# CON_PCI_Express_X1_36PIN.net
KiCad netlist of a schematic drawn in Altium Designer
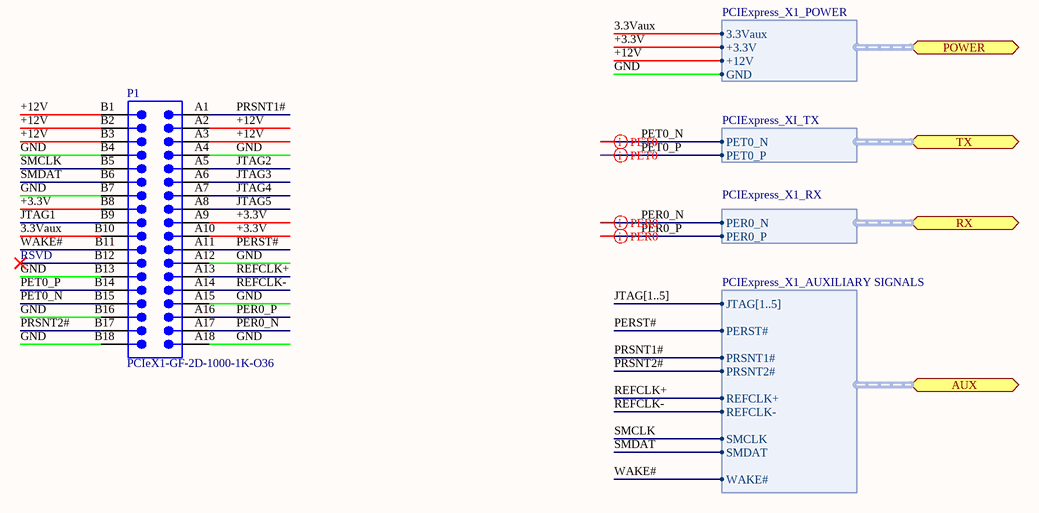
[diagram p0: CON_PCI_Express_X1_36PIN.SchDoc]

(export (version "E")
  (design (tool "Eeschema 10.0.6"))
  (components
    (comp (ref "P1")
      (value "PCIeX1-GF-2D-1000-1K-O36")
      (footprint "PCIeX1-GF-2D-1000-1K-O36")
      (description "Golden finger, PCIeX1, Dual, Opposite, Pitch 1mm, 36-Position")
      (fields (field (name "PUBLISHER") "Altium"))
      (libsource (lib "Altium Shanghai") (part "CMP-0001-00030-2"))
    )
  )
  (nets
    (net (code "6") (name "/+3.3V") (class "Default")
      (node (ref "P1") (pin "A10") (pinfunction "A10_A10") (pintype "passive"))
      (node (ref "P1") (pin "A9") (pinfunction "A9_A9") (pintype "passive"))
      (node (ref "P1") (pin "B8") (pinfunction "B8_B8") (pintype "passive"))
    )
    (net (code "7") (name "/+12V") (class "Default")
      (node (ref "P1") (pin "A2") (pinfunction "A2_A2") (pintype "passive"))
      (node (ref "P1") (pin "A3") (pinfunction "A3_A3") (pintype "passive"))
      (node (ref "P1") (pin "B1") (pinfunction "B1_B1") (pintype "passive"))
      (node (ref "P1") (pin "B2") (pinfunction "B2_B2") (pintype "passive"))
      (node (ref "P1") (pin "B3") (pinfunction "B3_B3") (pintype "passive"))
    )
    (net (code "8") (name "/3.3Vaux") (class "Default")
      (node (ref "P1") (pin "B10") (pinfunction "B10_B10") (pintype "passive"))
    )
    (net (code "9") (name "/GND") (class "Default")
      (node (ref "P1") (pin "A12") (pinfunction "A12_A12") (pintype "passive"))
      (node (ref "P1") (pin "A15") (pinfunction "A15_A15") (pintype "passive"))
      (node (ref "P1") (pin "A18") (pinfunction "A18_A18") (pintype "passive"))
      (node (ref "P1") (pin "A4") (pinfunction "A4_A4") (pintype "passive"))
      (node (ref "P1") (pin "B13") (pinfunction "B13_B13") (pintype "passive"))
      (node (ref "P1") (pin "B16") (pinfunction "B16_B16") (pintype "passive"))
      (node (ref "P1") (pin "B18") (pinfunction "B18_B18") (pintype "passive"))
      (node (ref "P1") (pin "B4") (pinfunction "B4_B4") (pintype "passive"))
      (node (ref "P1") (pin "B7") (pinfunction "B7_B7") (pintype "passive"))
    )
    (net (code "10") (name "/JTAG1") (class "Default")
      (node (ref "P1") (pin "B9") (pinfunction "B9_B9") (pintype "passive"))
    )
    (net (code "11") (name "/JTAG2") (class "Default")
      (node (ref "P1") (pin "A5") (pinfunction "A5_A5") (pintype "passive"))
    )
    (net (code "12") (name "/JTAG3") (class "Default")
      (node (ref "P1") (pin "A6") (pinfunction "A6_A6") (pintype "passive"))
    )
    (net (code "13") (name "/JTAG4") (class "Default")
      (node (ref "P1") (pin "A7") (pinfunction "A7_A7") (pintype "passive"))
    )
    (net (code "14") (name "/JTAG5") (class "Default")
      (node (ref "P1") (pin "A8") (pinfunction "A8_A8") (pintype "passive"))
    )
    (net (code "16") (name "/PER0_N") (class "Default")
      (node (ref "P1") (pin "A17") (pinfunction "A17_A17") (pintype "passive"))
    )
    (net (code "17") (name "/PER0_P") (class "Default")
      (node (ref "P1") (pin "A16") (pinfunction "A16_A16") (pintype "passive"))
    )
    (net (code "18") (name "/PERST#") (class "Default")
      (node (ref "P1") (pin "A11") (pinfunction "A11_A11") (pintype "passive"))
    )
    (net (code "19") (name "/PET0_N") (class "Default")
      (node (ref "P1") (pin "B15") (pinfunction "B15_B15") (pintype "passive"))
    )
    (net (code "20") (name "/PET0_P") (class "Default")
      (node (ref "P1") (pin "B14") (pinfunction "B14_B14") (pintype "passive"))
    )
    (net (code "21") (name "/PRSNT1#") (class "Default")
      (node (ref "P1") (pin "A1") (pinfunction "A1_A1") (pintype "passive"))
    )
    (net (code "22") (name "/PRSNT2#") (class "Default")
      (node (ref "P1") (pin "B17") (pinfunction "B17_B17") (pintype "passive"))
    )
    (net (code "23") (name "/REFCLK+") (class "Default")
      (node (ref "P1") (pin "A13") (pinfunction "A13_A13") (pintype "passive"))
    )
    (net (code "24") (name "/REFCLK-") (class "Default")
      (node (ref "P1") (pin "A14") (pinfunction "A14_A14") (pintype "passive"))
    )
    (net (code "25") (name "/SMCLK") (class "Default")
      (node (ref "P1") (pin "B5") (pinfunction "B5_B5") (pintype "passive"))
    )
    (net (code "26") (name "/SMDAT") (class "Default")
      (node (ref "P1") (pin "B6") (pinfunction "B6_B6") (pintype "passive"))
    )
    (net (code "27") (name "/WAKE#") (class "Default")
      (node (ref "P1") (pin "B11") (pinfunction "B11_B11") (pintype "passive"))
    )
    (net (code "32") (name "unconnected-(P1-PadB12)") (class "Default")
      (node (ref "P1") (pin "B12") (pinfunction "B12_B12") (pintype "passive+no_connect"))
    )
  )
)
